# iotester.net
KiCad netlist of a schematic drawn in EAGLE
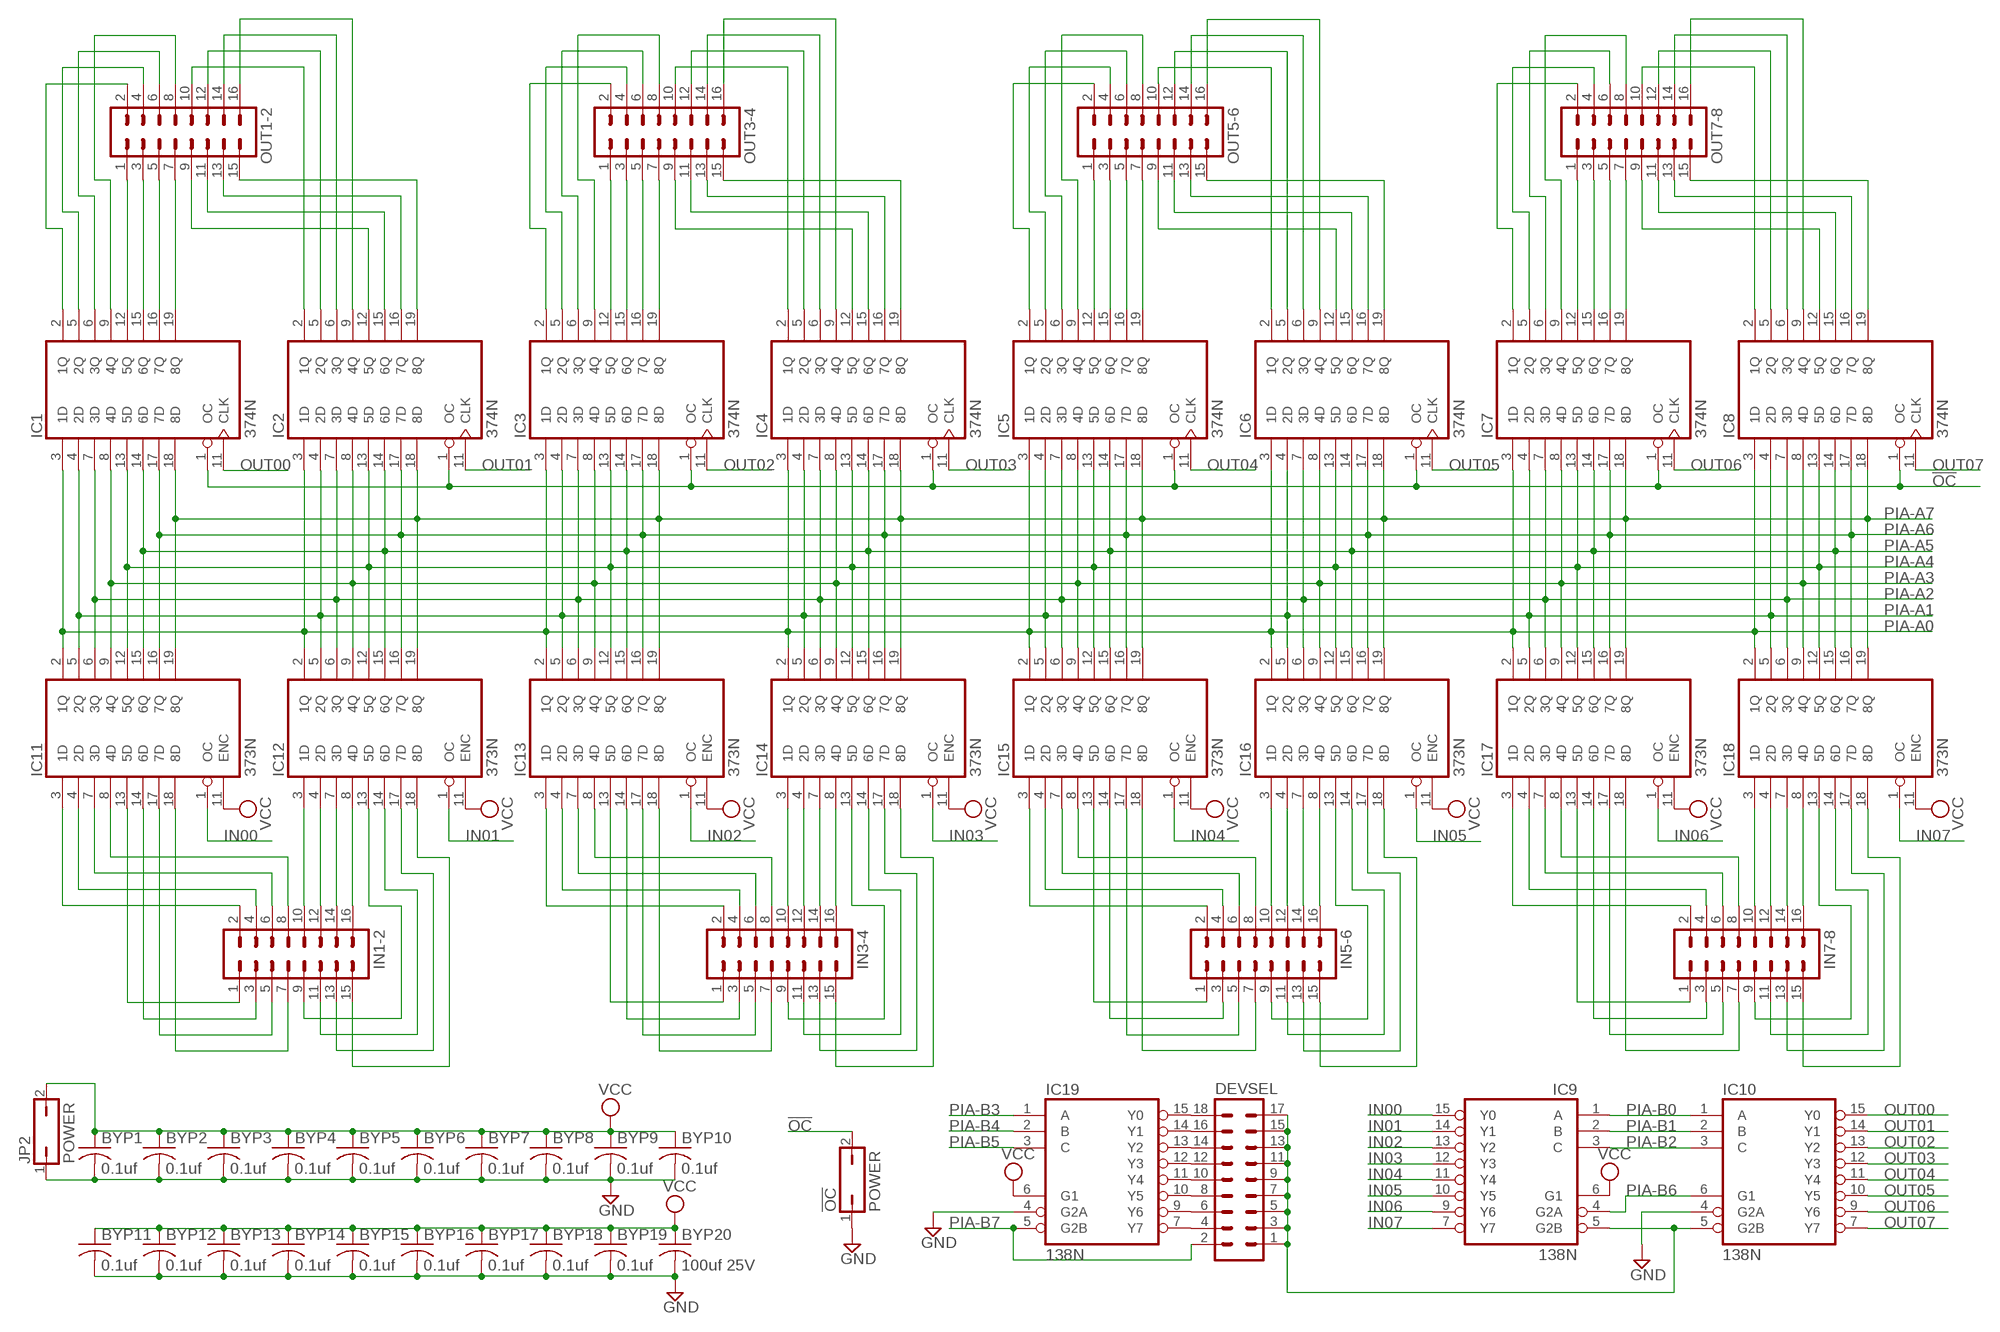
[diagram p0: schematic, sheet 1]
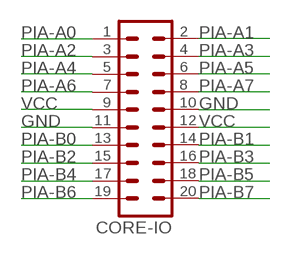
[diagram p1: schematic, sheet 2]

(export (version "E")
  (design (tool "Eeschema 10.0.6"))
  (components
    (comp (ref "!OC")
      (value "POWER")
      (footprint "eagle-import:JP1")
      (libsource (lib "eagle-import") (part "JP1Q"))
    )
    (comp (ref "BYP1")
      (value "0.1uf")
      (footprint "eagle-import:C050-025X075")
      (libsource (lib "eagle-import") (part "C-US050-025X075"))
    )
    (comp (ref "BYP2")
      (value "0.1uf")
      (footprint "eagle-import:C050-025X075")
      (libsource (lib "eagle-import") (part "C-US050-025X075"))
    )
    (comp (ref "BYP3")
      (value "0.1uf")
      (footprint "eagle-import:C050-025X075")
      (libsource (lib "eagle-import") (part "C-US050-025X075"))
    )
    (comp (ref "BYP4")
      (value "0.1uf")
      (footprint "eagle-import:C050-025X075")
      (libsource (lib "eagle-import") (part "C-US050-025X075"))
    )
    (comp (ref "BYP5")
      (value "0.1uf")
      (footprint "eagle-import:C050-025X075")
      (libsource (lib "eagle-import") (part "C-US050-025X075"))
    )
    (comp (ref "BYP6")
      (value "0.1uf")
      (footprint "eagle-import:C050-025X075")
      (libsource (lib "eagle-import") (part "C-US050-025X075"))
    )
    (comp (ref "BYP7")
      (value "0.1uf")
      (footprint "eagle-import:C050-025X075")
      (libsource (lib "eagle-import") (part "C-US050-025X075"))
    )
    (comp (ref "BYP8")
      (value "0.1uf")
      (footprint "eagle-import:C050-025X075")
      (libsource (lib "eagle-import") (part "C-US050-025X075"))
    )
    (comp (ref "BYP9")
      (value "0.1uf")
      (footprint "eagle-import:C050-025X075")
      (libsource (lib "eagle-import") (part "C-US050-025X075"))
    )
    (comp (ref "BYP10")
      (value "0.1uf")
      (footprint "eagle-import:C050-025X075")
      (libsource (lib "eagle-import") (part "C-US050-025X075"))
    )
    (comp (ref "BYP11")
      (value "0.1uf")
      (footprint "eagle-import:C050-025X075")
      (libsource (lib "eagle-import") (part "C-US050-025X075"))
    )
    (comp (ref "BYP12")
      (value "0.1uf")
      (footprint "eagle-import:C050-025X075")
      (libsource (lib "eagle-import") (part "C-US050-025X075"))
    )
    (comp (ref "BYP13")
      (value "0.1uf")
      (footprint "eagle-import:C050-025X075")
      (libsource (lib "eagle-import") (part "C-US050-025X075"))
    )
    (comp (ref "BYP14")
      (value "0.1uf")
      (footprint "eagle-import:C050-025X075")
      (libsource (lib "eagle-import") (part "C-US050-025X075"))
    )
    (comp (ref "BYP15")
      (value "0.1uf")
      (footprint "eagle-import:C050-025X075")
      (libsource (lib "eagle-import") (part "C-US050-025X075"))
    )
    (comp (ref "BYP16")
      (value "0.1uf")
      (footprint "eagle-import:C050-025X075")
      (libsource (lib "eagle-import") (part "C-US050-025X075"))
    )
    (comp (ref "BYP17")
      (value "0.1uf")
      (footprint "eagle-import:C050-025X075")
      (libsource (lib "eagle-import") (part "C-US050-025X075"))
    )
    (comp (ref "BYP18")
      (value "0.1uf")
      (footprint "eagle-import:C050-025X075")
      (libsource (lib "eagle-import") (part "C-US050-025X075"))
    )
    (comp (ref "BYP19")
      (value "0.1uf")
      (footprint "eagle-import:C050-025X075")
      (libsource (lib "eagle-import") (part "C-US050-025X075"))
    )
    (comp (ref "BYP20")
      (value "100uf 25V")
      (footprint "eagle-import:C150-064X183")
      (libsource (lib "eagle-import") (part "C-US150-064X183"))
    )
    (comp (ref "DEVSEL")
      (value "MA09-2")
      (footprint "eagle-import:MA09-2")
      (libsource (lib "eagle-import") (part "MA09-2"))
    )
    (comp (ref "IC1")
      (value "374N")
      (footprint "eagle-import:DIL20")
      (libsource (lib "eagle-import") (part "74374NLS"))
    )
    (comp (ref "IC2")
      (value "374N")
      (footprint "eagle-import:DIL20")
      (libsource (lib "eagle-import") (part "74374NLS"))
    )
    (comp (ref "IC3")
      (value "374N")
      (footprint "eagle-import:DIL20")
      (libsource (lib "eagle-import") (part "74374NLS"))
    )
    (comp (ref "IC4")
      (value "374N")
      (footprint "eagle-import:DIL20")
      (libsource (lib "eagle-import") (part "74374NLS"))
    )
    (comp (ref "IC5")
      (value "374N")
      (footprint "eagle-import:DIL20")
      (libsource (lib "eagle-import") (part "74374NLS"))
    )
    (comp (ref "IC6")
      (value "374N")
      (footprint "eagle-import:DIL20")
      (libsource (lib "eagle-import") (part "74374NLS"))
    )
    (comp (ref "IC7")
      (value "374N")
      (footprint "eagle-import:DIL20")
      (libsource (lib "eagle-import") (part "74374NLS"))
    )
    (comp (ref "IC8")
      (value "374N")
      (footprint "eagle-import:DIL20")
      (libsource (lib "eagle-import") (part "74374NLS"))
    )
    (comp (ref "IC9")
      (value "138N")
      (footprint "eagle-import:DIL16")
      (libsource (lib "eagle-import") (part "74138NLS"))
    )
    (comp (ref "IC10")
      (value "138N")
      (footprint "eagle-import:DIL16")
      (libsource (lib "eagle-import") (part "74138NLS"))
    )
    (comp (ref "IC11")
      (value "373N")
      (footprint "eagle-import:DIL20")
      (libsource (lib "eagle-import") (part "74373NLS"))
    )
    (comp (ref "IC12")
      (value "373N")
      (footprint "eagle-import:DIL20")
      (libsource (lib "eagle-import") (part "74373NLS"))
    )
    (comp (ref "IC13")
      (value "373N")
      (footprint "eagle-import:DIL20")
      (libsource (lib "eagle-import") (part "74373NLS"))
    )
    (comp (ref "IC14")
      (value "373N")
      (footprint "eagle-import:DIL20")
      (libsource (lib "eagle-import") (part "74373NLS"))
    )
    (comp (ref "IC15")
      (value "373N")
      (footprint "eagle-import:DIL20")
      (libsource (lib "eagle-import") (part "74373NLS"))
    )
    (comp (ref "IC16")
      (value "373N")
      (footprint "eagle-import:DIL20")
      (libsource (lib "eagle-import") (part "74373NLS"))
    )
    (comp (ref "IC17")
      (value "373N")
      (footprint "eagle-import:DIL20")
      (libsource (lib "eagle-import") (part "74373NLS"))
    )
    (comp (ref "IC18")
      (value "373N")
      (footprint "eagle-import:DIL20")
      (libsource (lib "eagle-import") (part "74373NLS"))
    )
    (comp (ref "IC19")
      (value "138N")
      (footprint "eagle-import:DIL16")
      (libsource (lib "eagle-import") (part "74138NLS"))
    )
    (comp (ref "IN1-2")
      (value "MA08-2")
      (footprint "eagle-import:MA08-2")
      (libsource (lib "eagle-import") (part "MA08-2"))
    )
    (comp (ref "IN3-4")
      (value "MA08-2")
      (footprint "eagle-import:MA08-2")
      (libsource (lib "eagle-import") (part "MA08-2"))
    )
    (comp (ref "IN5-6")
      (value "MA08-2")
      (footprint "eagle-import:MA08-2")
      (libsource (lib "eagle-import") (part "MA08-2"))
    )
    (comp (ref "IN7-8")
      (value "MA08-2")
      (footprint "eagle-import:MA08-2")
      (libsource (lib "eagle-import") (part "MA08-2"))
    )
    (comp (ref "JP2")
      (value "POWER")
      (footprint "eagle-import:JP1")
      (libsource (lib "eagle-import") (part "JP1Q"))
    )
    (comp (ref "OUT1-2")
      (value "MA08-2")
      (footprint "eagle-import:MA08-2")
      (libsource (lib "eagle-import") (part "MA08-2"))
    )
    (comp (ref "OUT3-4")
      (value "MA08-2")
      (footprint "eagle-import:MA08-2")
      (libsource (lib "eagle-import") (part "MA08-2"))
    )
    (comp (ref "OUT5-6")
      (value "MA08-2")
      (footprint "eagle-import:MA08-2")
      (libsource (lib "eagle-import") (part "MA08-2"))
    )
    (comp (ref "OUT7-8")
      (value "MA08-2")
      (footprint "eagle-import:MA08-2")
      (libsource (lib "eagle-import") (part "MA08-2"))
    )
    (comp (ref "CORE-IO")
      (value "MA10-2")
      (footprint "eagle-import:MA10-2")
      (libsource (lib "eagle-import") (part "MA10-2"))
    )
  )
  (nets
    (net (code "1") (name "GND") (class "Default")
      (node (ref "!OC") (pin "1") (pinfunction "1_1") (pintype "passive"))
      (node (ref "BYP1") (pin "2") (pinfunction "2_2") (pintype "passive"))
      (node (ref "BYP10") (pin "2") (pinfunction "2_2") (pintype "passive"))
      (node (ref "BYP11") (pin "2") (pinfunction "2_2") (pintype "passive"))
      (node (ref "BYP12") (pin "2") (pinfunction "2_2") (pintype "passive"))
      (node (ref "BYP13") (pin "2") (pinfunction "2_2") (pintype "passive"))
      (node (ref "BYP14") (pin "2") (pinfunction "2_2") (pintype "passive"))
      (node (ref "BYP15") (pin "2") (pinfunction "2_2") (pintype "passive"))
      (node (ref "BYP16") (pin "2") (pinfunction "2_2") (pintype "passive"))
      (node (ref "BYP17") (pin "2") (pinfunction "2_2") (pintype "passive"))
      (node (ref "BYP18") (pin "2") (pinfunction "2_2") (pintype "passive"))
      (node (ref "BYP19") (pin "2") (pinfunction "2_2") (pintype "passive"))
      (node (ref "BYP2") (pin "2") (pinfunction "2_2") (pintype "passive"))
      (node (ref "BYP20") (pin "2") (pinfunction "2_2") (pintype "passive"))
      (node (ref "BYP3") (pin "2") (pinfunction "2_2") (pintype "passive"))
      (node (ref "BYP4") (pin "2") (pinfunction "2_2") (pintype "passive"))
      (node (ref "BYP5") (pin "2") (pinfunction "2_2") (pintype "passive"))
      (node (ref "BYP6") (pin "2") (pinfunction "2_2") (pintype "passive"))
      (node (ref "BYP7") (pin "2") (pinfunction "2_2") (pintype "passive"))
      (node (ref "BYP8") (pin "2") (pinfunction "2_2") (pintype "passive"))
      (node (ref "BYP9") (pin "2") (pinfunction "2_2") (pintype "passive"))
      (node (ref "CORE-IO") (pin "10") (pinfunction "10_10") (pintype "passive"))
      (node (ref "CORE-IO") (pin "11") (pinfunction "11_11") (pintype "passive"))
      (node (ref "IC10") (pin "4") (pinfunction "G2A_4") (pintype "input"))
      (node (ref "IC19") (pin "4") (pinfunction "G2A_4") (pintype "input"))
      (node (ref "JP2") (pin "1") (pinfunction "1_1") (pintype "passive"))
    )
    (net (code "2") (name "IN00") (class "Default")
      (node (ref "IC11") (pin "1") (pinfunction "OC_1") (pintype "input"))
      (node (ref "IC9") (pin "15") (pinfunction "Y0_15") (pintype "output"))
    )
    (net (code "3") (name "IN01") (class "Default")
      (node (ref "IC12") (pin "1") (pinfunction "OC_1") (pintype "input"))
      (node (ref "IC9") (pin "14") (pinfunction "Y1_14") (pintype "output"))
    )
    (net (code "4") (name "IN02") (class "Default")
      (node (ref "IC13") (pin "1") (pinfunction "OC_1") (pintype "input"))
      (node (ref "IC9") (pin "13") (pinfunction "Y2_13") (pintype "output"))
    )
    (net (code "5") (name "IN03") (class "Default")
      (node (ref "IC14") (pin "1") (pinfunction "OC_1") (pintype "input"))
      (node (ref "IC9") (pin "12") (pinfunction "Y3_12") (pintype "output"))
    )
    (net (code "6") (name "IN04") (class "Default")
      (node (ref "IC15") (pin "1") (pinfunction "OC_1") (pintype "input"))
      (node (ref "IC9") (pin "11") (pinfunction "Y4_11") (pintype "output"))
    )
    (net (code "7") (name "IN05") (class "Default")
      (node (ref "IC16") (pin "1") (pinfunction "OC_1") (pintype "input"))
      (node (ref "IC9") (pin "10") (pinfunction "Y5_10") (pintype "output"))
    )
    (net (code "8") (name "IN06") (class "Default")
      (node (ref "IC17") (pin "1") (pinfunction "OC_1") (pintype "input"))
      (node (ref "IC9") (pin "9") (pinfunction "Y6_9") (pintype "output"))
    )
    (net (code "9") (name "IN07") (class "Default")
      (node (ref "IC18") (pin "1") (pinfunction "OC_1") (pintype "input"))
      (node (ref "IC9") (pin "7") (pinfunction "Y7_7") (pintype "output"))
    )
    (net (code "10") (name "Net-(IC1A-1Q)") (class "Default")
      (node (ref "IC1") (pin "2") (pinfunction "1Q_2") (pintype "tri_state"))
      (node (ref "OUT1-2") (pin "2") (pinfunction "2_2") (pintype "passive"))
    )
    (net (code "11") (name "Net-(IC1A-2Q)") (class "Default")
      (node (ref "IC1") (pin "5") (pinfunction "2Q_5") (pintype "tri_state"))
      (node (ref "OUT1-2") (pin "4") (pinfunction "4_4") (pintype "passive"))
    )
    (net (code "12") (name "Net-(IC1A-3Q)") (class "Default")
      (node (ref "IC1") (pin "6") (pinfunction "3Q_6") (pintype "tri_state"))
      (node (ref "OUT1-2") (pin "6") (pinfunction "6_6") (pintype "passive"))
    )
    (net (code "13") (name "Net-(IC1A-4Q)") (class "Default")
      (node (ref "IC1") (pin "9") (pinfunction "4Q_9") (pintype "tri_state"))
      (node (ref "OUT1-2") (pin "8") (pinfunction "8_8") (pintype "passive"))
    )
    (net (code "14") (name "Net-(IC1A-5Q)") (class "Default")
      (node (ref "IC1") (pin "12") (pinfunction "5Q_12") (pintype "tri_state"))
      (node (ref "OUT1-2") (pin "1") (pinfunction "1_1") (pintype "passive"))
    )
    (net (code "15") (name "Net-(IC1A-6Q)") (class "Default")
      (node (ref "IC1") (pin "15") (pinfunction "6Q_15") (pintype "tri_state"))
      (node (ref "OUT1-2") (pin "3") (pinfunction "3_3") (pintype "passive"))
    )
    (net (code "16") (name "Net-(IC1A-7Q)") (class "Default")
      (node (ref "IC1") (pin "16") (pinfunction "7Q_16") (pintype "tri_state"))
      (node (ref "OUT1-2") (pin "5") (pinfunction "5_5") (pintype "passive"))
    )
    (net (code "17") (name "Net-(IC1A-8Q)") (class "Default")
      (node (ref "IC1") (pin "19") (pinfunction "8Q_19") (pintype "tri_state"))
      (node (ref "OUT1-2") (pin "7") (pinfunction "7_7") (pintype "passive"))
    )
    (net (code "18") (name "Net-(IC2A-1Q)") (class "Default")
      (node (ref "IC2") (pin "2") (pinfunction "1Q_2") (pintype "tri_state"))
      (node (ref "OUT1-2") (pin "10") (pinfunction "10_10") (pintype "passive"))
    )
    (net (code "19") (name "Net-(IC2A-2Q)") (class "Default")
      (node (ref "IC2") (pin "5") (pinfunction "2Q_5") (pintype "tri_state"))
      (node (ref "OUT1-2") (pin "12") (pinfunction "12_12") (pintype "passive"))
    )
    (net (code "20") (name "Net-(IC2A-3Q)") (class "Default")
      (node (ref "IC2") (pin "6") (pinfunction "3Q_6") (pintype "tri_state"))
      (node (ref "OUT1-2") (pin "14") (pinfunction "14_14") (pintype "passive"))
    )
    (net (code "21") (name "Net-(IC2A-4Q)") (class "Default")
      (node (ref "IC2") (pin "9") (pinfunction "4Q_9") (pintype "tri_state"))
      (node (ref "OUT1-2") (pin "16") (pinfunction "16_16") (pintype "passive"))
    )
    (net (code "22") (name "Net-(IC2A-5Q)") (class "Default")
      (node (ref "IC2") (pin "12") (pinfunction "5Q_12") (pintype "tri_state"))
      (node (ref "OUT1-2") (pin "9") (pinfunction "9_9") (pintype "passive"))
    )
    (net (code "23") (name "Net-(IC2A-6Q)") (class "Default")
      (node (ref "IC2") (pin "15") (pinfunction "6Q_15") (pintype "tri_state"))
      (node (ref "OUT1-2") (pin "11") (pinfunction "11_11") (pintype "passive"))
    )
    (net (code "24") (name "Net-(IC2A-7Q)") (class "Default")
      (node (ref "IC2") (pin "16") (pinfunction "7Q_16") (pintype "tri_state"))
      (node (ref "OUT1-2") (pin "13") (pinfunction "13_13") (pintype "passive"))
    )
    (net (code "25") (name "Net-(IC2A-8Q)") (class "Default")
      (node (ref "IC2") (pin "19") (pinfunction "8Q_19") (pintype "tri_state"))
      (node (ref "OUT1-2") (pin "15") (pinfunction "15_15") (pintype "passive"))
    )
    (net (code "26") (name "Net-(IC3A-1Q)") (class "Default")
      (node (ref "IC3") (pin "2") (pinfunction "1Q_2") (pintype "tri_state"))
      (node (ref "OUT3-4") (pin "2") (pinfunction "2_2") (pintype "passive"))
    )
    (net (code "27") (name "Net-(IC3A-2Q)") (class "Default")
      (node (ref "IC3") (pin "5") (pinfunction "2Q_5") (pintype "tri_state"))
      (node (ref "OUT3-4") (pin "4") (pinfunction "4_4") (pintype "passive"))
    )
    (net (code "28") (name "Net-(IC3A-3Q)") (class "Default")
      (node (ref "IC3") (pin "6") (pinfunction "3Q_6") (pintype "tri_state"))
      (node (ref "OUT3-4") (pin "6") (pinfunction "6_6") (pintype "passive"))
    )
    (net (code "29") (name "Net-(IC3A-4Q)") (class "Default")
      (node (ref "IC3") (pin "9") (pinfunction "4Q_9") (pintype "tri_state"))
      (node (ref "OUT3-4") (pin "8") (pinfunction "8_8") (pintype "passive"))
    )
    (net (code "30") (name "Net-(IC3A-5Q)") (class "Default")
      (node (ref "IC3") (pin "12") (pinfunction "5Q_12") (pintype "tri_state"))
      (node (ref "OUT3-4") (pin "1") (pinfunction "1_1") (pintype "passive"))
    )
    (net (code "31") (name "Net-(IC3A-6Q)") (class "Default")
      (node (ref "IC3") (pin "15") (pinfunction "6Q_15") (pintype "tri_state"))
      (node (ref "OUT3-4") (pin "3") (pinfunction "3_3") (pintype "passive"))
    )
    (net (code "32") (name "Net-(IC3A-7Q)") (class "Default")
      (node (ref "IC3") (pin "16") (pinfunction "7Q_16") (pintype "tri_state"))
      (node (ref "OUT3-4") (pin "5") (pinfunction "5_5") (pintype "passive"))
    )
    (net (code "33") (name "Net-(IC3A-8Q)") (class "Default")
      (node (ref "IC3") (pin "19") (pinfunction "8Q_19") (pintype "tri_state"))
      (node (ref "OUT3-4") (pin "7") (pinfunction "7_7") (pintype "passive"))
    )
    (net (code "34") (name "Net-(IC4A-1Q)") (class "Default")
      (node (ref "IC4") (pin "2") (pinfunction "1Q_2") (pintype "tri_state"))
      (node (ref "OUT3-4") (pin "10") (pinfunction "10_10") (pintype "passive"))
    )
    (net (code "35") (name "Net-(IC4A-2Q)") (class "Default")
      (node (ref "IC4") (pin "5") (pinfunction "2Q_5") (pintype "tri_state"))
      (node (ref "OUT3-4") (pin "12") (pinfunction "12_12") (pintype "passive"))
    )
    (net (code "36") (name "Net-(IC4A-3Q)") (class "Default")
      (node (ref "IC4") (pin "6") (pinfunction "3Q_6") (pintype "tri_state"))
      (node (ref "OUT3-4") (pin "14") (pinfunction "14_14") (pintype "passive"))
    )
    (net (code "37") (name "Net-(IC4A-4Q)") (class "Default")
      (node (ref "IC4") (pin "9") (pinfunction "4Q_9") (pintype "tri_state"))
      (node (ref "OUT3-4") (pin "16") (pinfunction "16_16") (pintype "passive"))
    )
    (net (code "38") (name "Net-(IC4A-5Q)") (class "Default")
      (node (ref "IC4") (pin "12") (pinfunction "5Q_12") (pintype "tri_state"))
      (node (ref "OUT3-4") (pin "9") (pinfunction "9_9") (pintype "passive"))
    )
    (net (code "39") (name "Net-(IC4A-6Q)") (class "Default")
      (node (ref "IC4") (pin "15") (pinfunction "6Q_15") (pintype "tri_state"))
      (node (ref "OUT3-4") (pin "11") (pinfunction "11_11") (pintype "passive"))
    )
    (net (code "40") (name "Net-(IC4A-7Q)") (class "Default")
      (node (ref "IC4") (pin "16") (pinfunction "7Q_16") (pintype "tri_state"))
      (node (ref "OUT3-4") (pin "13") (pinfunction "13_13") (pintype "passive"))
    )
    (net (code "41") (name "Net-(IC4A-8Q)") (class "Default")
      (node (ref "IC4") (pin "19") (pinfunction "8Q_19") (pintype "tri_state"))
      (node (ref "OUT3-4") (pin "15") (pinfunction "15_15") (pintype "passive"))
    )
    (net (code "42") (name "Net-(IC5A-1Q)") (class "Default")
      (node (ref "IC5") (pin "2") (pinfunction "1Q_2") (pintype "tri_state"))
      (node (ref "OUT5-6") (pin "2") (pinfunction "2_2") (pintype "passive"))
    )
    (net (code "43") (name "Net-(IC5A-2Q)") (class "Default")
      (node (ref "IC5") (pin "5") (pinfunction "2Q_5") (pintype "tri_state"))
      (node (ref "OUT5-6") (pin "4") (pinfunction "4_4") (pintype "passive"))
    )
    (net (code "44") (name "Net-(IC5A-3Q)") (class "Default")
      (node (ref "IC5") (pin "6") (pinfunction "3Q_6") (pintype "tri_state"))
      (node (ref "OUT5-6") (pin "6") (pinfunction "6_6") (pintype "passive"))
    )
    (net (code "45") (name "Net-(IC5A-4Q)") (class "Default")
      (node (ref "IC5") (pin "9") (pinfunction "4Q_9") (pintype "tri_state"))
      (node (ref "OUT5-6") (pin "8") (pinfunction "8_8") (pintype "passive"))
    )
    (net (code "46") (name "Net-(IC5A-5Q)") (class "Default")
      (node (ref "IC5") (pin "12") (pinfunction "5Q_12") (pintype "tri_state"))
      (node (ref "OUT5-6") (pin "1") (pinfunction "1_1") (pintype "passive"))
    )
    (net (code "47") (name "Net-(IC5A-6Q)") (class "Default")
      (node (ref "IC5") (pin "15") (pinfunction "6Q_15") (pintype "tri_state"))
      (node (ref "OUT5-6") (pin "3") (pinfunction "3_3") (pintype "passive"))
    )
    (net (code "48") (name "Net-(IC5A-7Q)") (class "Default")
      (node (ref "IC5") (pin "16") (pinfunction "7Q_16") (pintype "tri_state"))
      (node (ref "OUT5-6") (pin "5") (pinfunction "5_5") (pintype "passive"))
    )
    (net (code "49") (name "Net-(IC5A-8Q)") (class "Default")
      (node (ref "IC5") (pin "19") (pinfunction "8Q_19") (pintype "tri_state"))
      (node (ref "OUT5-6") (pin "7") (pinfunction "7_7") (pintype "passive"))
    )
    (net (code "50") (name "Net-(IC6A-1Q)") (class "Default")
      (node (ref "IC6") (pin "2") (pinfunction "1Q_2") (pintype "tri_state"))
      (node (ref "OUT5-6") (pin "10") (pinfunction "10_10") (pintype "passive"))
    )
    (net (code "51") (name "Net-(IC6A-2Q)") (class "Default")
      (node (ref "IC6") (pin "5") (pinfunction "2Q_5") (pintype "tri_state"))
      (node (ref "OUT5-6") (pin "12") (pinfunction "12_12") (pintype "passive"))
    )
    (net (code "52") (name "Net-(IC6A-3Q)") (class "Default")
      (node (ref "IC6") (pin "6") (pinfunction "3Q_6") (pintype "tri_state"))
      (node (ref "OUT5-6") (pin "14") (pinfunction "14_14") (pintype "passive"))
    )
    (net (code "53") (name "Net-(IC6A-4Q)") (class "Default")
      (node (ref "IC6") (pin "9") (pinfunction "4Q_9") (pintype "tri_state"))
      (node (ref "OUT5-6") (pin "16") (pinfunction "16_16") (pintype "passive"))
    )
    (net (code "54") (name "Net-(IC6A-5Q)") (class "Default")
      (node (ref "IC6") (pin "12") (pinfunction "5Q_12") (pintype "tri_state"))
      (node (ref "OUT5-6") (pin "9") (pinfunction "9_9") (pintype "passive"))
    )
    (net (code "55") (name "Net-(IC6A-6Q)") (class "Default")
      (node (ref "IC6") (pin "15") (pinfunction "6Q_15") (pintype "tri_state"))
      (node (ref "OUT5-6") (pin "11") (pinfunction "11_11") (pintype "passive"))
    )
    (net (code "56") (name "Net-(IC6A-7Q)") (class "Default")
      (node (ref "IC6") (pin "16") (pinfunction "7Q_16") (pintype "tri_state"))
      (node (ref "OUT5-6") (pin "13") (pinfunction "13_13") (pintype "passive"))
    )
    (net (code "57") (name "Net-(IC6A-8Q)") (class "Default")
      (node (ref "IC6") (pin "19") (pinfunction "8Q_19") (pintype "tri_state"))
      (node (ref "OUT5-6") (pin "15") (pinfunction "15_15") (pintype "passive"))
    )
    (net (code "58") (name "Net-(IC7A-1Q)") (class "Default")
      (node (ref "IC7") (pin "2") (pinfunction "1Q_2") (pintype "tri_state"))
      (node (ref "OUT7-8") (pin "2") (pinfunction "2_2") (pintype "passive"))
    )
    (net (code "59") (name "Net-(IC7A-2Q)") (class "Default")
      (node (ref "IC7") (pin "5") (pinfunction "2Q_5") (pintype "tri_state"))
      (node (ref "OUT7-8") (pin "4") (pinfunction "4_4") (pintype "passive"))
    )
    (net (code "60") (name "Net-(IC7A-3Q)") (class "Default")
      (node (ref "IC7") (pin "6") (pinfunction "3Q_6") (pintype "tri_state"))
      (node (ref "OUT7-8") (pin "6") (pinfunction "6_6") (pintype "passive"))
    )
    (net (code "61") (name "Net-(IC7A-4Q)") (class "Default")
      (node (ref "IC7") (pin "9") (pinfunction "4Q_9") (pintype "tri_state"))
      (node (ref "OUT7-8") (pin "8") (pinfunction "8_8") (pintype "passive"))
    )
    (net (code "62") (name "Net-(IC7A-5Q)") (class "Default")
      (node (ref "IC7") (pin "12") (pinfunction "5Q_12") (pintype "tri_state"))
      (node (ref "OUT7-8") (pin "1") (pinfunction "1_1") (pintype "passive"))
    )
    (net (code "63") (name "Net-(IC7A-6Q)") (class "Default")
      (node (ref "IC7") (pin "15") (pinfunction "6Q_15") (pintype "tri_state"))
      (node (ref "OUT7-8") (pin "3") (pinfunction "3_3") (pintype "passive"))
    )
    (net (code "64") (name "Net-(IC7A-7Q)") (class "Default")
      (node (ref "IC7") (pin "16") (pinfunction "7Q_16") (pintype "tri_state"))
      (node (ref "OUT7-8") (pin "5") (pinfunction "5_5") (pintype "passive"))
    )
    (net (code "65") (name "Net-(IC7A-8Q)") (class "Default")
      (node (ref "IC7") (pin "19") (pinfunction "8Q_19") (pintype "tri_state"))
      (node (ref "OUT7-8") (pin "7") (pinfunction "7_7") (pintype "passive"))
    )
    (net (code "66") (name "Net-(IC8A-1Q)") (class "Default")
      (node (ref "IC8") (pin "2") (pinfunction "1Q_2") (pintype "tri_state"))
      (node (ref "OUT7-8") (pin "10") (pinfunction "10_10") (pintype "passive"))
    )
    (net (code "67") (name "Net-(IC8A-2Q)") (class "Default")
      (node (ref "IC8") (pin "5") (pinfunction "2Q_5") (pintype "tri_state"))
      (node (ref "OUT7-8") (pin "12") (pinfunction "12_12") (pintype "passive"))
    )
    (net (code "68") (name "Net-(IC8A-3Q)") (class "Default")
      (node (ref "IC8") (pin "6") (pinfunction "3Q_6") (pintype "tri_state"))
      (node (ref "OUT7-8") (pin "14") (pinfunction "14_14") (pintype "passive"))
    )
    (net (code "69") (name "Net-(IC8A-4Q)") (class "Default")
      (node (ref "IC8") (pin "9") (pinfunction "4Q_9") (pintype "tri_state"))
      (node (ref "OUT7-8") (pin "16") (pinfunction "16_16") (pintype "passive"))
    )
    (net (code "70") (name "Net-(IC8A-5Q)") (class "Default")
      (node (ref "IC8") (pin "12") (pinfunction "5Q_12") (pintype "tri_state"))
      (node (ref "OUT7-8") (pin "9") (pinfunction "9_9") (pintype "passive"))
    )
    (net (code "71") (name "Net-(IC8A-6Q)") (class "Default")
      (node (ref "IC8") (pin "15") (pinfunction "6Q_15") (pintype "tri_state"))
      (node (ref "OUT7-8") (pin "11") (pinfunction "11_11") (pintype "passive"))
    )
    (net (code "72") (name "Net-(IC8A-7Q)") (class "Default")
      (node (ref "IC8") (pin "16") (pinfunction "7Q_16") (pintype "tri_state"))
      (node (ref "OUT7-8") (pin "13") (pinfunction "13_13") (pintype "passive"))
    )
    (net (code "73") (name "Net-(IC8A-8Q)") (class "Default")
      (node (ref "IC8") (pin "19") (pinfunction "8Q_19") (pintype "tri_state"))
      (node (ref "OUT7-8") (pin "15") (pinfunction "15_15") (pintype "passive"))
    )
    (net (code "74") (name "Net-(IC10A-G2B)") (class "Default")
      (node (ref "DEVSEL") (pin "1") (pinfunction "1_1") (pintype "passive"))
      (node (ref "DEVSEL") (pin "11") (pinfunction "11_11") (pintype "passive"))
      (node (ref "DEVSEL") (pin "13") (pinfunction "13_13") (pintype "passive"))
      (node (ref "DEVSEL") (pin "15") (pinfunction "15_15") (pintype "passive"))
      (node (ref "DEVSEL") (pin "17") (pinfunction "17_17") (pintype "passive"))
      (node (ref "DEVSEL") (pin "3") (pinfunction "3_3") (pintype "passive"))
      (node (ref "DEVSEL") (pin "5") (pinfunction "5_5") (pintype "passive"))
      (node (ref "DEVSEL") (pin "7") (pinfunction "7_7") (pintype "passive"))
      (node (ref "DEVSEL") (pin "9") (pinfunction "9_9") (pintype "passive"))
      (node (ref "IC10") (pin "5") (pinfunction "G2B_5") (pintype "input"))
      (node (ref "IC9") (pin "5") (pinfunction "G2B_5") (pintype "input"))
    )
    (net (code "75") (name "Net-(IC11A-1D)") (class "Default")
      (node (ref "IC11") (pin "3") (pinfunction "1D_3") (pintype "input"))
      (node (ref "IN1-2") (pin "2") (pinfunction "2_2") (pintype "passive"))
    )
    (net (code "76") (name "Net-(IC11A-2D)") (class "Default")
      (node (ref "IC11") (pin "4") (pinfunction "2D_4") (pintype "input"))
      (node (ref "IN1-2") (pin "4") (pinfunction "4_4") (pintype "passive"))
    )
    (net (code "77") (name "Net-(IC11A-3D)") (class "Default")
      (node (ref "IC11") (pin "7") (pinfunction "3D_7") (pintype "input"))
      (node (ref "IN1-2") (pin "6") (pinfunction "6_6") (pintype "passive"))
    )
    (net (code "78") (name "Net-(IC11A-4D)") (class "Default")
      (node (ref "IC11") (pin "8") (pinfunction "4D_8") (pintype "input"))
      (node (ref "IN1-2") (pin "8") (pinfunction "8_8") (pintype "passive"))
    )
    (net (code "79") (name "Net-(IC11A-5D)") (class "Default")
      (node (ref "IC11") (pin "13") (pinfunction "5D_13") (pintype "input"))
      (node (ref "IN1-2") (pin "1") (pinfunction "1_1") (pintype "passive"))
    )
    (net (code "80") (name "Net-(IC11A-6D)") (class "Default")
      (node (ref "IC11") (pin "14") (pinfunction "6D_14") (pintype "input"))
      (node (ref "IN1-2") (pin "3") (pinfunction "3_3") (pintype "passive"))
    )
    (net (code "81") (name "Net-(IC11A-7D)") (class "Default")
      (node (ref "IC11") (pin "17") (pinfunction "7D_17") (pintype "input"))
      (node (ref "IN1-2") (pin "5") (pinfunction "5_5") (pintype "passive"))
    )
    (net (code "82") (name "Net-(IC11A-8D)") (class "Default")
      (node (ref "IC11") (pin "18") (pinfunction "8D_18") (pintype "input"))
      (node (ref "IN1-2") (pin "7") (pinfunction "7_7") (pintype "passive"))
    )
    (net (code "83") (name "Net-(IC12A-1D)") (class "Default")
      (node (ref "IC12") (pin "3") (pinfunction "1D_3") (pintype "input"))
      (node (ref "IN1-2") (pin "10") (pinfunction "10_10") (pintype "passive"))
    )
    (net (code "84") (name "Net-(IC12A-2D)") (class "Default")
      (node (ref "IC12") (pin "4") (pinfunction "2D_4") (pintype "input"))
      (node (ref "IN1-2") (pin "12") (pinfunction "12_12") (pintype "passive"))
    )
    (net (code "85") (name "Net-(IC12A-3D)") (class "Default")
      (node (ref "IC12") (pin "7") (pinfunction "3D_7") (pintype "input"))
      (node (ref "IN1-2") (pin "14") (pinfunction "14_14") (pintype "passive"))
    )
    (net (code "86") (name "Net-(IC12A-4D)") (class "Default")
      (node (ref "IC12") (pin "8") (pinfunction "4D_8") (pintype "input"))
      (node (ref "IN1-2") (pin "16") (pinfunction "16_16") (pintype "passive"))
    )
    (net (code "87") (name "Net-(IC12A-5D)") (class "Default")
      (node (ref "IC12") (pin "13") (pinfunction "5D_13") (pintype "input"))
      (node (ref "IN1-2") (pin "9") (pinfunction "9_9") (pintype "passive"))
    )
    (net (code "88") (name "Net-(IC12A-6D)") (class "Default")
      (node (ref "IC12") (pin "14") (pinfunction "6D_14") (pintype "input"))
      (node (ref "IN1-2") (pin "11") (pinfunction "11_11") (pintype "passive"))
    )
    (net (code "89") (name "Net-(IC12A-7D)") (class "Default")
      (node (ref "IC12") (pin "17") (pinfunction "7D_17") (pintype "input"))
      (node (ref "IN1-2") (pin "13") (pinfunction "13_13") (pintype "passive"))
    )
    (net (code "90") (name "Net-(IC12A-8D)") (class "Default")
      (node (ref "IC12") (pin "18") (pinfunction "8D_18") (pintype "input"))
      (node (ref "IN1-2") (pin "15") (pinfunction "15_15") (pintype "passive"))
    )
    (net (code "91") (name "Net-(IC13A-1D)") (class "Default")
      (node (ref "IC13") (pin "3") (pinfunction "1D_3") (pintype "input"))
      (node (ref "IN3-4") (pin "2") (pinfunction "2_2") (pintype "passive"))
    )
    (net (code "92") (name "Net-(IC13A-2D)") (class "Default")
      (node (ref "IC13") (pin "4") (pinfunction "2D_4") (pintype "input"))
      (node (ref "IN3-4") (pin "4") (pinfunction "4_4") (pintype "passive"))
    )
    (net (code "93") (name "Net-(IC13A-3D)") (class "Default")
      (node (ref "IC13") (pin "7") (pinfunction "3D_7") (pintype "input"))
      (node (ref "IN3-4") (pin "6") (pinfunction "6_6") (pintype "passive"))
    )
    (net (code "94") (name "Net-(IC13A-4D)") (class "Default")
      (node (ref "IC13") (pin "8") (pinfunction "4D_8") (pintype "input"))
      (node (ref "IN3-4") (pin "8") (pinfunction "8_8") (pintype "passive"))
    )
    (net (code "95") (name "Net-(IC13A-5D)") (class "Default")
      (node (ref "IC13") (pin "13") (pinfunction "5D_13") (pintype "input"))
      (node (ref "IN3-4") (pin "1") (pinfunction "1_1") (pintype "passive"))
    )
    (net (code "96") (name "Net-(IC13A-6D)") (class "Default")
      (node (ref "IC13") (pin "14") (pinfunction "6D_14") (pintype "input"))
      (node (ref "IN3-4") (pin "3") (pinfunction "3_3") (pintype "passive"))
    )
    (net (code "97") (name "Net-(IC13A-7D)") (class "Default")
      (node (ref "IC13") (pin "17") (pinfunction "7D_17") (pintype "input"))
      (node (ref "IN3-4") (pin "5") (pinfunction "5_5") (pintype "passive"))
    )
    (net (code "98") (name "Net-(IC13A-8D)") (class "Default")
      (node (ref "IC13") (pin "18") (pinfunction "8D_18") (pintype "input"))
      (node (ref "IN3-4") (pin "7") (pinfunction "7_7") (pintype "passive"))
    )
    (net (code "99") (name "Net-(IC14A-1D)") (class "Default")
      (node (ref "IC14") (pin "3") (pinfunction "1D_3") (pintype "input"))
      (node (ref "IN3-4") (pin "10") (pinfunction "10_10") (pintype "passive"))
    )
    (net (code "100") (name "Net-(IC14A-2D)") (class "Default")
      (node (ref "IC14") (pin "4") (pinfunction "2D_4") (pintype "input"))
      (node (ref "IN3-4") (pin "12") (pinfunction "12_12") (pintype "passive"))
    )
    (net (code "101") (name "Net-(IC14A-3D)") (class "Default")
      (node (ref "IC14") (pin "7") (pinfunction "3D_7") (pintype "input"))
      (node (ref "IN3-4") (pin "14") (pinfunction "14_14") (pintype "passive"))
    )
    (net (code "102") (name "Net-(IC14A-4D)") (class "Default")
      (node (ref "IC14") (pin "8") (pinfunction "4D_8") (pintype "input"))
      (node (ref "IN3-4") (pin "16") (pinfunction "16_16") (pintype "passive"))
    )
    (net (code "103") (name "Net-(IC14A-5D)") (class "Default")
      (node (ref "IC14") (pin "13") (pinfunction "5D_13") (pintype "input"))
      (node (ref "IN3-4") (pin "9") (pinfunction "9_9") (pintype "passive"))
    )
    (net (code "104") (name "Net-(IC14A-6D)") (class "Default")
      (node (ref "IC14") (pin "14") (pinfunction "6D_14") (pintype "input"))
      (node (ref "IN3-4") (pin "11") (pinfunction "11_11") (pintype "passive"))
    )
    (net (code "105") (name "Net-(IC14A-7D)") (class "Default")
      (node (ref "IC14") (pin "17") (pinfunction "7D_17") (pintype "input"))
      (node (ref "IN3-4") (pin "13") (pinfunction "13_13") (pintype "passive"))
    )
    (net (code "106") (name "Net-(IC14A-8D)") (class "Default")
      (node (ref "IC14") (pin "18") (pinfunction "8D_18") (pintype "input"))
      (node (ref "IN3-4") (pin "15") (pinfunction "15_15") (pintype "passive"))
    )
    (net (code "107") (name "Net-(IC15A-1D)") (class "Default")
      (node (ref "IC15") (pin "3") (pinfunction "1D_3") (pintype "input"))
      (node (ref "IN5-6") (pin "2") (pinfunction "2_2") (pintype "passive"))
    )
    (net (code "108") (name "Net-(IC15A-2D)") (class "Default")
      (node (ref "IC15") (pin "4") (pinfunction "2D_4") (pintype "input"))
      (node (ref "IN5-6") (pin "4") (pinfunction "4_4") (pintype "passive"))
    )
    (net (code "109") (name "Net-(IC15A-3D)") (class "Default")
      (node (ref "IC15") (pin "7") (pinfunction "3D_7") (pintype "input"))
      (node (ref "IN5-6") (pin "6") (pinfunction "6_6") (pintype "passive"))
    )
    (net (code "110") (name "Net-(IC15A-4D)") (class "Default")
      (node (ref "IC15") (pin "8") (pinfunction "4D_8") (pintype "input"))
      (node (ref "IN5-6") (pin "8") (pinfunction "8_8") (pintype "passive"))
    )
    (net (code "111") (name "Net-(IC15A-5D)") (class "Default")
      (node (ref "IC15") (pin "13") (pinfunction "5D_13") (pintype "input"))
      (node (ref "IN5-6") (pin "1") (pinfunction "1_1") (pintype "passive"))
    )
    (net (code "112") (name "Net-(IC15A-6D)") (class "Default")
      (node (ref "IC15") (pin "14") (pinfunction "6D_14") (pintype "input"))
      (node (ref "IN5-6") (pin "3") (pinfunction "3_3") (pintype "passive"))
    )
    (net (code "113") (name "Net-(IC15A-7D)") (class "Default")
      (node (ref "IC15") (pin "17") (pinfunction "7D_17") (pintype "input"))
      (node (ref "IN5-6") (pin "5") (pinfunction "5_5") (pintype "passive"))
    )
    (net (code "114") (name "Net-(IC15A-8D)") (class "Default")
      (node (ref "IC15") (pin "18") (pinfunction "8D_18") (pintype "input"))
      (node (ref "IN5-6") (pin "7") (pinfunction "7_7") (pintype "passive"))
    )
    (net (code "115") (name "Net-(IC16A-1D)") (class "Default")
      (node (ref "IC16") (pin "3") (pinfunction "1D_3") (pintype "input"))
      (node (ref "IN5-6") (pin "10") (pinfunction "10_10") (pintype "passive"))
    )
    (net (code "116") (name "Net-(IC16A-2D)") (class "Default")
      (node (ref "IC16") (pin "4") (pinfunction "2D_4") (pintype "input"))
      (node (ref "IN5-6") (pin "12") (pinfunction "12_12") (pintype "passive"))
    )
    (net (code "117") (name "Net-(IC16A-3D)") (class "Default")
      (node (ref "IC16") (pin "7") (pinfunction "3D_7") (pintype "input"))
      (node (ref "IN5-6") (pin "14") (pinfunction "14_14") (pintype "passive"))
    )
    (net (code "118") (name "Net-(IC16A-4D)") (class "Default")
      (node (ref "IC16") (pin "8") (pinfunction "4D_8") (pintype "input"))
      (node (ref "IN5-6") (pin "16") (pinfunction "16_16") (pintype "passive"))
    )
    (net (code "119") (name "Net-(IC16A-5D)") (class "Default")
      (node (ref "IC16") (pin "13") (pinfunction "5D_13") (pintype "input"))
      (node (ref "IN5-6") (pin "9") (pinfunction "9_9") (pintype "passive"))
    )
    (net (code "120") (name "Net-(IC16A-6D)") (class "Default")
      (node (ref "IC16") (pin "14") (pinfunction "6D_14") (pintype "input"))
      (node (ref "IN5-6") (pin "11") (pinfunction "11_11") (pintype "passive"))
    )
    (net (code "121") (name "Net-(IC16A-7D)") (class "Default")
      (node (ref "IC16") (pin "17") (pinfunction "7D_17") (pintype "input"))
      (node (ref "IN5-6") (pin "13") (pinfunction "13_13") (pintype "passive"))
    )
    (net (code "122") (name "Net-(IC16A-8D)") (class "Default")
      (node (ref "IC16") (pin "18") (pinfunction "8D_18") (pintype "input"))
      (node (ref "IN5-6") (pin "15") (pinfunction "15_15") (pintype "passive"))
    )
    (net (code "123") (name "Net-(IC17A-1D)") (class "Default")
      (node (ref "IC17") (pin "3") (pinfunction "1D_3") (pintype "input"))
      (node (ref "IN7-8") (pin "2") (pinfunction "2_2") (pintype "passive"))
    )
    (net (code "124") (name "Net-(IC17A-2D)") (class "Default")
      (node (ref "IC17") (pin "4") (pinfunction "2D_4") (pintype "input"))
      (node (ref "IN7-8") (pin "4") (pinfunction "4_4") (pintype "passive"))
    )
    (net (code "125") (name "Net-(IC17A-3D)") (class "Default")
      (node (ref "IC17") (pin "7") (pinfunction "3D_7") (pintype "input"))
      (node (ref "IN7-8") (pin "6") (pinfunction "6_6") (pintype "passive"))
    )
    (net (code "126") (name "Net-(IC17A-4D)") (class "Default")
      (node (ref "IC17") (pin "8") (pinfunction "4D_8") (pintype "input"))
      (node (ref "IN7-8") (pin "8") (pinfunction "8_8") (pintype "passive"))
    )
    (net (code "127") (name "Net-(IC17A-5D)") (class "Default")
      (node (ref "IC17") (pin "13") (pinfunction "5D_13") (pintype "input"))
      (node (ref "IN7-8") (pin "1") (pinfunction "1_1") (pintype "passive"))
    )
    (net (code "128") (name "Net-(IC17A-6D)") (class "Default")
      (node (ref "IC17") (pin "14") (pinfunction "6D_14") (pintype "input"))
      (node (ref "IN7-8") (pin "3") (pinfunction "3_3") (pintype "passive"))
    )
    (net (code "129") (name "Net-(IC17A-7D)") (class "Default")
      (node (ref "IC17") (pin "17") (pinfunction "7D_17") (pintype "input"))
      (node (ref "IN7-8") (pin "5") (pinfunction "5_5") (pintype "passive"))
    )
    (net (code "130") (name "Net-(IC17A-8D)") (class "Default")
      (node (ref "IC17") (pin "18") (pinfunction "8D_18") (pintype "input"))
      (node (ref "IN7-8") (pin "7") (pinfunction "7_7") (pintype "passive"))
    )
    (net (code "131") (name "Net-(IC18A-1D)") (class "Default")
      (node (ref "IC18") (pin "3") (pinfunction "1D_3") (pintype "input"))
      (node (ref "IN7-8") (pin "10") (pinfunction "10_10") (pintype "passive"))
    )
    (net (code "132") (name "Net-(IC18A-2D)") (class "Default")
      (node (ref "IC18") (pin "4") (pinfunction "2D_4") (pintype "input"))
      (node (ref "IN7-8") (pin "12") (pinfunction "12_12") (pintype "passive"))
    )
    (net (code "133") (name "Net-(IC18A-3D)") (class "Default")
      (node (ref "IC18") (pin "7") (pinfunction "3D_7") (pintype "input"))
      (node (ref "IN7-8") (pin "14") (pinfunction "14_14") (pintype "passive"))
    )
    (net (code "134") (name "Net-(IC18A-4D)") (class "Default")
      (node (ref "IC18") (pin "8") (pinfunction "4D_8") (pintype "input"))
      (node (ref "IN7-8") (pin "16") (pinfunction "16_16") (pintype "passive"))
    )
    (net (code "135") (name "Net-(IC18A-5D)") (class "Default")
      (node (ref "IC18") (pin "13") (pinfunction "5D_13") (pintype "input"))
      (node (ref "IN7-8") (pin "9") (pinfunction "9_9") (pintype "passive"))
    )
    (net (code "136") (name "Net-(IC18A-6D)") (class "Default")
      (node (ref "IC18") (pin "14") (pinfunction "6D_14") (pintype "input"))
      (node (ref "IN7-8") (pin "11") (pinfunction "11_11") (pintype "passive"))
    )
    (net (code "137") (name "Net-(IC18A-7D)") (class "Default")
      (node (ref "IC18") (pin "17") (pinfunction "7D_17") (pintype "input"))
      (node (ref "IN7-8") (pin "13") (pinfunction "13_13") (pintype "passive"))
    )
    (net (code "138") (name "Net-(IC18A-8D)") (class "Default")
      (node (ref "IC18") (pin "18") (pinfunction "8D_18") (pintype "input"))
      (node (ref "IN7-8") (pin "15") (pinfunction "15_15") (pintype "passive"))
    )
    (net (code "139") (name "Net-(IC19A-Y0)") (class "Default")
      (node (ref "DEVSEL") (pin "18") (pinfunction "18_18") (pintype "passive"))
      (node (ref "IC19") (pin "15") (pinfunction "Y0_15") (pintype "output"))
    )
    (net (code "140") (name "Net-(IC19A-Y1)") (class "Default")
      (node (ref "DEVSEL") (pin "16") (pinfunction "16_16") (pintype "passive"))
      (node (ref "IC19") (pin "14") (pinfunction "Y1_14") (pintype "output"))
    )
    (net (code "141") (name "Net-(IC19A-Y2)") (class "Default")
      (node (ref "DEVSEL") (pin "14") (pinfunction "14_14") (pintype "passive"))
      (node (ref "IC19") (pin "13") (pinfunction "Y2_13") (pintype "output"))
    )
    (net (code "142") (name "Net-(IC19A-Y3)") (class "Default")
      (node (ref "DEVSEL") (pin "12") (pinfunction "12_12") (pintype "passive"))
      (node (ref "IC19") (pin "12") (pinfunction "Y3_12") (pintype "output"))
    )
    (net (code "143") (name "Net-(IC19A-Y4)") (class "Default")
      (node (ref "DEVSEL") (pin "10") (pinfunction "10_10") (pintype "passive"))
      (node (ref "IC19") (pin "11") (pinfunction "Y4_11") (pintype "output"))
    )
    (net (code "144") (name "Net-(IC19A-Y5)") (class "Default")
      (node (ref "DEVSEL") (pin "8") (pinfunction "8_8") (pintype "passive"))
      (node (ref "IC19") (pin "10") (pinfunction "Y5_10") (pintype "output"))
    )
    (net (code "145") (name "Net-(IC19A-Y6)") (class "Default")
      (node (ref "DEVSEL") (pin "6") (pinfunction "6_6") (pintype "passive"))
      (node (ref "IC19") (pin "9") (pinfunction "Y6_9") (pintype "output"))
    )
    (net (code "146") (name "Net-(IC19A-Y7)") (class "Default")
      (node (ref "DEVSEL") (pin "4") (pinfunction "4_4") (pintype "passive"))
      (node (ref "IC19") (pin "7") (pinfunction "Y7_7") (pintype "output"))
    )
    (net (code "147") (name "OUT00") (class "Default")
      (node (ref "IC1") (pin "11") (pinfunction "CLK_11") (pintype "input"))
      (node (ref "IC10") (pin "15") (pinfunction "Y0_15") (pintype "output"))
    )
    (net (code "148") (name "OUT01") (class "Default")
      (node (ref "IC10") (pin "14") (pinfunction "Y1_14") (pintype "output"))
      (node (ref "IC2") (pin "11") (pinfunction "CLK_11") (pintype "input"))
    )
    (net (code "149") (name "OUT02") (class "Default")
      (node (ref "IC10") (pin "13") (pinfunction "Y2_13") (pintype "output"))
      (node (ref "IC3") (pin "11") (pinfunction "CLK_11") (pintype "input"))
    )
    (net (code "150") (name "OUT03") (class "Default")
      (node (ref "IC10") (pin "12") (pinfunction "Y3_12") (pintype "output"))
      (node (ref "IC4") (pin "11") (pinfunction "CLK_11") (pintype "input"))
    )
    (net (code "151") (name "OUT04") (class "Default")
      (node (ref "IC10") (pin "11") (pinfunction "Y4_11") (pintype "output"))
      (node (ref "IC5") (pin "11") (pinfunction "CLK_11") (pintype "input"))
    )
    (net (code "152") (name "OUT05") (class "Default")
      (node (ref "IC10") (pin "10") (pinfunction "Y5_10") (pintype "output"))
      (node (ref "IC6") (pin "11") (pinfunction "CLK_11") (pintype "input"))
    )
    (net (code "153") (name "OUT06") (class "Default")
      (node (ref "IC10") (pin "9") (pinfunction "Y6_9") (pintype "output"))
      (node (ref "IC7") (pin "11") (pinfunction "CLK_11") (pintype "input"))
    )
    (net (code "154") (name "OUT07") (class "Default")
      (node (ref "IC10") (pin "7") (pinfunction "Y7_7") (pintype "output"))
      (node (ref "IC8") (pin "11") (pinfunction "CLK_11") (pintype "input"))
    )
    (net (code "155") (name "PIA-A0") (class "Default")
      (node (ref "CORE-IO") (pin "1") (pinfunction "1_1") (pintype "passive"))
      (node (ref "IC1") (pin "3") (pinfunction "1D_3") (pintype "input"))
      (node (ref "IC11") (pin "2") (pinfunction "1Q_2") (pintype "tri_state"))
      (node (ref "IC12") (pin "2") (pinfunction "1Q_2") (pintype "tri_state"))
      (node (ref "IC13") (pin "2") (pinfunction "1Q_2") (pintype "tri_state"))
      (node (ref "IC14") (pin "2") (pinfunction "1Q_2") (pintype "tri_state"))
      (node (ref "IC15") (pin "2") (pinfunction "1Q_2") (pintype "tri_state"))
      (node (ref "IC16") (pin "2") (pinfunction "1Q_2") (pintype "tri_state"))
      (node (ref "IC17") (pin "2") (pinfunction "1Q_2") (pintype "tri_state"))
      (node (ref "IC18") (pin "2") (pinfunction "1Q_2") (pintype "tri_state"))
      (node (ref "IC2") (pin "3") (pinfunction "1D_3") (pintype "input"))
      (node (ref "IC3") (pin "3") (pinfunction "1D_3") (pintype "input"))
      (node (ref "IC4") (pin "3") (pinfunction "1D_3") (pintype "input"))
      (node (ref "IC5") (pin "3") (pinfunction "1D_3") (pintype "input"))
      (node (ref "IC6") (pin "3") (pinfunction "1D_3") (pintype "input"))
      (node (ref "IC7") (pin "3") (pinfunction "1D_3") (pintype "input"))
      (node (ref "IC8") (pin "3") (pinfunction "1D_3") (pintype "input"))
    )
    (net (code "156") (name "PIA-A1") (class "Default")
      (node (ref "CORE-IO") (pin "2") (pinfunction "2_2") (pintype "passive"))
      (node (ref "IC1") (pin "4") (pinfunction "2D_4") (pintype "input"))
      (node (ref "IC11") (pin "5") (pinfunction "2Q_5") (pintype "tri_state"))
      (node (ref "IC12") (pin "5") (pinfunction "2Q_5") (pintype "tri_state"))
      (node (ref "IC13") (pin "5") (pinfunction "2Q_5") (pintype "tri_state"))
      (node (ref "IC14") (pin "5") (pinfunction "2Q_5") (pintype "tri_state"))
      (node (ref "IC15") (pin "5") (pinfunction "2Q_5") (pintype "tri_state"))
      (node (ref "IC16") (pin "5") (pinfunction "2Q_5") (pintype "tri_state"))
      (node (ref "IC17") (pin "5") (pinfunction "2Q_5") (pintype "tri_state"))
      (node (ref "IC18") (pin "5") (pinfunction "2Q_5") (pintype "tri_state"))
      (node (ref "IC2") (pin "4") (pinfunction "2D_4") (pintype "input"))
      (node (ref "IC3") (pin "4") (pinfunction "2D_4") (pintype "input"))
      (node (ref "IC4") (pin "4") (pinfunction "2D_4") (pintype "input"))
      (node (ref "IC5") (pin "4") (pinfunction "2D_4") (pintype "input"))
      (node (ref "IC6") (pin "4") (pinfunction "2D_4") (pintype "input"))
      (node (ref "IC7") (pin "4") (pinfunction "2D_4") (pintype "input"))
      (node (ref "IC8") (pin "4") (pinfunction "2D_4") (pintype "input"))
    )
    (net (code "157") (name "PIA-A2") (class "Default")
      (node (ref "CORE-IO") (pin "3") (pinfunction "3_3") (pintype "passive"))
      (node (ref "IC1") (pin "7") (pinfunction "3D_7") (pintype "input"))
      (node (ref "IC11") (pin "6") (pinfunction "3Q_6") (pintype "tri_state"))
      (node (ref "IC12") (pin "6") (pinfunction "3Q_6") (pintype "tri_state"))
      (node (ref "IC13") (pin "6") (pinfunction "3Q_6") (pintype "tri_state"))
      (node (ref "IC14") (pin "6") (pinfunction "3Q_6") (pintype "tri_state"))
      (node (ref "IC15") (pin "6") (pinfunction "3Q_6") (pintype "tri_state"))
      (node (ref "IC16") (pin "6") (pinfunction "3Q_6") (pintype "tri_state"))
      (node (ref "IC17") (pin "6") (pinfunction "3Q_6") (pintype "tri_state"))
      (node (ref "IC18") (pin "6") (pinfunction "3Q_6") (pintype "tri_state"))
      (node (ref "IC2") (pin "7") (pinfunction "3D_7") (pintype "input"))
      (node (ref "IC3") (pin "7") (pinfunction "3D_7") (pintype "input"))
      (node (ref "IC4") (pin "7") (pinfunction "3D_7") (pintype "input"))
      (node (ref "IC5") (pin "7") (pinfunction "3D_7") (pintype "input"))
      (node (ref "IC6") (pin "7") (pinfunction "3D_7") (pintype "input"))
      (node (ref "IC7") (pin "7") (pinfunction "3D_7") (pintype "input"))
      (node (ref "IC8") (pin "7") (pinfunction "3D_7") (pintype "input"))
    )
    (net (code "158") (name "PIA-A3") (class "Default")
      (node (ref "CORE-IO") (pin "4") (pinfunction "4_4") (pintype "passive"))
      (node (ref "IC1") (pin "8") (pinfunction "4D_8") (pintype "input"))
      (node (ref "IC11") (pin "9") (pinfunction "4Q_9") (pintype "tri_state"))
      (node (ref "IC12") (pin "9") (pinfunction "4Q_9") (pintype "tri_state"))
      (node (ref "IC13") (pin "9") (pinfunction "4Q_9") (pintype "tri_state"))
      (node (ref "IC14") (pin "9") (pinfunction "4Q_9") (pintype "tri_state"))
      (node (ref "IC15") (pin "9") (pinfunction "4Q_9") (pintype "tri_state"))
      (node (ref "IC16") (pin "9") (pinfunction "4Q_9") (pintype "tri_state"))
      (node (ref "IC17") (pin "9") (pinfunction "4Q_9") (pintype "tri_state"))
      (node (ref "IC18") (pin "9") (pinfunction "4Q_9") (pintype "tri_state"))
      (node (ref "IC2") (pin "8") (pinfunction "4D_8") (pintype "input"))
      (node (ref "IC3") (pin "8") (pinfunction "4D_8") (pintype "input"))
      (node (ref "IC4") (pin "8") (pinfunction "4D_8") (pintype "input"))
      (node (ref "IC5") (pin "8") (pinfunction "4D_8") (pintype "input"))
      (node (ref "IC6") (pin "8") (pinfunction "4D_8") (pintype "input"))
      (node (ref "IC7") (pin "8") (pinfunction "4D_8") (pintype "input"))
      (node (ref "IC8") (pin "8") (pinfunction "4D_8") (pintype "input"))
    )
    (net (code "159") (name "PIA-A4") (class "Default")
      (node (ref "CORE-IO") (pin "5") (pinfunction "5_5") (pintype "passive"))
      (node (ref "IC1") (pin "13") (pinfunction "5D_13") (pintype "input"))
      (node (ref "IC11") (pin "12") (pinfunction "5Q_12") (pintype "tri_state"))
      (node (ref "IC12") (pin "12") (pinfunction "5Q_12") (pintype "tri_state"))
      (node (ref "IC13") (pin "12") (pinfunction "5Q_12") (pintype "tri_state"))
      (node (ref "IC14") (pin "12") (pinfunction "5Q_12") (pintype "tri_state"))
      (node (ref "IC15") (pin "12") (pinfunction "5Q_12") (pintype "tri_state"))
      (node (ref "IC16") (pin "12") (pinfunction "5Q_12") (pintype "tri_state"))
      (node (ref "IC17") (pin "12") (pinfunction "5Q_12") (pintype "tri_state"))
      (node (ref "IC18") (pin "12") (pinfunction "5Q_12") (pintype "tri_state"))
      (node (ref "IC2") (pin "13") (pinfunction "5D_13") (pintype "input"))
      (node (ref "IC3") (pin "13") (pinfunction "5D_13") (pintype "input"))
      (node (ref "IC4") (pin "13") (pinfunction "5D_13") (pintype "input"))
      (node (ref "IC5") (pin "13") (pinfunction "5D_13") (pintype "input"))
      (node (ref "IC6") (pin "13") (pinfunction "5D_13") (pintype "input"))
      (node (ref "IC7") (pin "13") (pinfunction "5D_13") (pintype "input"))
      (node (ref "IC8") (pin "13") (pinfunction "5D_13") (pintype "input"))
    )
    (net (code "160") (name "PIA-A5") (class "Default")
      (node (ref "CORE-IO") (pin "6") (pinfunction "6_6") (pintype "passive"))
      (node (ref "IC1") (pin "14") (pinfunction "6D_14") (pintype "input"))
      (node (ref "IC11") (pin "15") (pinfunction "6Q_15") (pintype "tri_state"))
      (node (ref "IC12") (pin "15") (pinfunction "6Q_15") (pintype "tri_state"))
      (node (ref "IC13") (pin "15") (pinfunction "6Q_15") (pintype "tri_state"))
      (node (ref "IC14") (pin "15") (pinfunction "6Q_15") (pintype "tri_state"))
      (node (ref "IC15") (pin "15") (pinfunction "6Q_15") (pintype "tri_state"))
      (node (ref "IC16") (pin "15") (pinfunction "6Q_15") (pintype "tri_state"))
      (node (ref "IC17") (pin "15") (pinfunction "6Q_15") (pintype "tri_state"))
      (node (ref "IC18") (pin "15") (pinfunction "6Q_15") (pintype "tri_state"))
      (node (ref "IC2") (pin "14") (pinfunction "6D_14") (pintype "input"))
      (node (ref "IC3") (pin "14") (pinfunction "6D_14") (pintype "input"))
      (node (ref "IC4") (pin "14") (pinfunction "6D_14") (pintype "input"))
      (node (ref "IC5") (pin "14") (pinfunction "6D_14") (pintype "input"))
      (node (ref "IC6") (pin "14") (pinfunction "6D_14") (pintype "input"))
      (node (ref "IC7") (pin "14") (pinfunction "6D_14") (pintype "input"))
      (node (ref "IC8") (pin "14") (pinfunction "6D_14") (pintype "input"))
    )
    (net (code "161") (name "PIA-A6") (class "Default")
      (node (ref "CORE-IO") (pin "7") (pinfunction "7_7") (pintype "passive"))
      (node (ref "IC1") (pin "17") (pinfunction "7D_17") (pintype "input"))
      (node (ref "IC11") (pin "16") (pinfunction "7Q_16") (pintype "tri_state"))
      (node (ref "IC12") (pin "16") (pinfunction "7Q_16") (pintype "tri_state"))
      (node (ref "IC13") (pin "16") (pinfunction "7Q_16") (pintype "tri_state"))
      (node (ref "IC14") (pin "16") (pinfunction "7Q_16") (pintype "tri_state"))
      (node (ref "IC15") (pin "16") (pinfunction "7Q_16") (pintype "tri_state"))
      (node (ref "IC16") (pin "16") (pinfunction "7Q_16") (pintype "tri_state"))
      (node (ref "IC17") (pin "16") (pinfunction "7Q_16") (pintype "tri_state"))
      (node (ref "IC18") (pin "16") (pinfunction "7Q_16") (pintype "tri_state"))
      (node (ref "IC2") (pin "17") (pinfunction "7D_17") (pintype "input"))
      (node (ref "IC3") (pin "17") (pinfunction "7D_17") (pintype "input"))
      (node (ref "IC4") (pin "17") (pinfunction "7D_17") (pintype "input"))
      (node (ref "IC5") (pin "17") (pinfunction "7D_17") (pintype "input"))
      (node (ref "IC6") (pin "17") (pinfunction "7D_17") (pintype "input"))
      (node (ref "IC7") (pin "17") (pinfunction "7D_17") (pintype "input"))
      (node (ref "IC8") (pin "17") (pinfunction "7D_17") (pintype "input"))
    )
    (net (code "162") (name "PIA-A7") (class "Default")
      (node (ref "CORE-IO") (pin "8") (pinfunction "8_8") (pintype "passive"))
      (node (ref "IC1") (pin "18") (pinfunction "8D_18") (pintype "input"))
      (node (ref "IC11") (pin "19") (pinfunction "8Q_19") (pintype "tri_state"))
      (node (ref "IC12") (pin "19") (pinfunction "8Q_19") (pintype "tri_state"))
      (node (ref "IC13") (pin "19") (pinfunction "8Q_19") (pintype "tri_state"))
      (node (ref "IC14") (pin "19") (pinfunction "8Q_19") (pintype "tri_state"))
      (node (ref "IC15") (pin "19") (pinfunction "8Q_19") (pintype "tri_state"))
      (node (ref "IC16") (pin "19") (pinfunction "8Q_19") (pintype "tri_state"))
      (node (ref "IC17") (pin "19") (pinfunction "8Q_19") (pintype "tri_state"))
      (node (ref "IC18") (pin "19") (pinfunction "8Q_19") (pintype "tri_state"))
      (node (ref "IC2") (pin "18") (pinfunction "8D_18") (pintype "input"))
      (node (ref "IC3") (pin "18") (pinfunction "8D_18") (pintype "input"))
      (node (ref "IC4") (pin "18") (pinfunction "8D_18") (pintype "input"))
      (node (ref "IC5") (pin "18") (pinfunction "8D_18") (pintype "input"))
      (node (ref "IC6") (pin "18") (pinfunction "8D_18") (pintype "input"))
      (node (ref "IC7") (pin "18") (pinfunction "8D_18") (pintype "input"))
      (node (ref "IC8") (pin "18") (pinfunction "8D_18") (pintype "input"))
    )
    (net (code "163") (name "PIA-B0") (class "Default")
      (node (ref "CORE-IO") (pin "13") (pinfunction "13_13") (pintype "passive"))
      (node (ref "IC10") (pin "1") (pinfunction "A_1") (pintype "input"))
      (node (ref "IC9") (pin "1") (pinfunction "A_1") (pintype "input"))
    )
    (net (code "164") (name "PIA-B1") (class "Default")
      (node (ref "CORE-IO") (pin "14") (pinfunction "14_14") (pintype "passive"))
      (node (ref "IC10") (pin "2") (pinfunction "B_2") (pintype "input"))
      (node (ref "IC9") (pin "2") (pinfunction "B_2") (pintype "input"))
    )
    (net (code "165") (name "PIA-B2") (class "Default")
      (node (ref "CORE-IO") (pin "15") (pinfunction "15_15") (pintype "passive"))
      (node (ref "IC10") (pin "3") (pinfunction "C_3") (pintype "input"))
      (node (ref "IC9") (pin "3") (pinfunction "C_3") (pintype "input"))
    )
    (net (code "166") (name "PIA-B3") (class "Default")
      (node (ref "CORE-IO") (pin "16") (pinfunction "16_16") (pintype "passive"))
      (node (ref "IC19") (pin "1") (pinfunction "A_1") (pintype "input"))
    )
    (net (code "167") (name "PIA-B4") (class "Default")
      (node (ref "CORE-IO") (pin "17") (pinfunction "17_17") (pintype "passive"))
      (node (ref "IC19") (pin "2") (pinfunction "B_2") (pintype "input"))
    )
    (net (code "168") (name "PIA-B5") (class "Default")
      (node (ref "CORE-IO") (pin "18") (pinfunction "18_18") (pintype "passive"))
      (node (ref "IC19") (pin "3") (pinfunction "C_3") (pintype "input"))
    )
    (net (code "169") (name "PIA-B6") (class "Default")
      (node (ref "CORE-IO") (pin "19") (pinfunction "19_19") (pintype "passive"))
      (node (ref "IC10") (pin "6") (pinfunction "G1_6") (pintype "input"))
      (node (ref "IC9") (pin "4") (pinfunction "G2A_4") (pintype "input"))
    )
    (net (code "170") (name "PIA-B7") (class "Default")
      (node (ref "CORE-IO") (pin "20") (pinfunction "20_20") (pintype "passive"))
      (node (ref "DEVSEL") (pin "2") (pinfunction "2_2") (pintype "passive"))
      (node (ref "IC19") (pin "5") (pinfunction "G2B_5") (pintype "input"))
    )
    (net (code "171") (name "VCC") (class "Default")
      (node (ref "BYP1") (pin "1") (pinfunction "1_1") (pintype "passive"))
      (node (ref "BYP10") (pin "1") (pinfunction "1_1") (pintype "passive"))
      (node (ref "BYP11") (pin "1") (pinfunction "1_1") (pintype "passive"))
      (node (ref "BYP12") (pin "1") (pinfunction "1_1") (pintype "passive"))
      (node (ref "BYP13") (pin "1") (pinfunction "1_1") (pintype "passive"))
      (node (ref "BYP14") (pin "1") (pinfunction "1_1") (pintype "passive"))
      (node (ref "BYP15") (pin "1") (pinfunction "1_1") (pintype "passive"))
      (node (ref "BYP16") (pin "1") (pinfunction "1_1") (pintype "passive"))
      (node (ref "BYP17") (pin "1") (pinfunction "1_1") (pintype "passive"))
      (node (ref "BYP18") (pin "1") (pinfunction "1_1") (pintype "passive"))
      (node (ref "BYP19") (pin "1") (pinfunction "1_1") (pintype "passive"))
      (node (ref "BYP2") (pin "1") (pinfunction "1_1") (pintype "passive"))
      (node (ref "BYP20") (pin "1") (pinfunction "1_1") (pintype "passive"))
      (node (ref "BYP3") (pin "1") (pinfunction "1_1") (pintype "passive"))
      (node (ref "BYP4") (pin "1") (pinfunction "1_1") (pintype "passive"))
      (node (ref "BYP5") (pin "1") (pinfunction "1_1") (pintype "passive"))
      (node (ref "BYP6") (pin "1") (pinfunction "1_1") (pintype "passive"))
      (node (ref "BYP7") (pin "1") (pinfunction "1_1") (pintype "passive"))
      (node (ref "BYP8") (pin "1") (pinfunction "1_1") (pintype "passive"))
      (node (ref "BYP9") (pin "1") (pinfunction "1_1") (pintype "passive"))
      (node (ref "CORE-IO") (pin "12") (pinfunction "12_12") (pintype "passive"))
      (node (ref "CORE-IO") (pin "9") (pinfunction "9_9") (pintype "passive"))
      (node (ref "IC11") (pin "11") (pinfunction "ENC_11") (pintype "input"))
      (node (ref "IC12") (pin "11") (pinfunction "ENC_11") (pintype "input"))
      (node (ref "IC13") (pin "11") (pinfunction "ENC_11") (pintype "input"))
      (node (ref "IC14") (pin "11") (pinfunction "ENC_11") (pintype "input"))
      (node (ref "IC15") (pin "11") (pinfunction "ENC_11") (pintype "input"))
      (node (ref "IC16") (pin "11") (pinfunction "ENC_11") (pintype "input"))
      (node (ref "IC17") (pin "11") (pinfunction "ENC_11") (pintype "input"))
      (node (ref "IC18") (pin "11") (pinfunction "ENC_11") (pintype "input"))
      (node (ref "IC19") (pin "6") (pinfunction "G1_6") (pintype "input"))
      (node (ref "IC9") (pin "6") (pinfunction "G1_6") (pintype "input"))
      (node (ref "JP2") (pin "2") (pinfunction "2_2") (pintype "passive"))
    )
    (net (code "172") (name "~{OC}") (class "Default")
      (node (ref "!OC") (pin "2") (pinfunction "2_2") (pintype "passive"))
      (node (ref "IC1") (pin "1") (pinfunction "OC_1") (pintype "input"))
      (node (ref "IC2") (pin "1") (pinfunction "OC_1") (pintype "input"))
      (node (ref "IC3") (pin "1") (pinfunction "OC_1") (pintype "input"))
      (node (ref "IC4") (pin "1") (pinfunction "OC_1") (pintype "input"))
      (node (ref "IC5") (pin "1") (pinfunction "OC_1") (pintype "input"))
      (node (ref "IC6") (pin "1") (pinfunction "OC_1") (pintype "input"))
      (node (ref "IC7") (pin "1") (pinfunction "OC_1") (pintype "input"))
      (node (ref "IC8") (pin "1") (pinfunction "OC_1") (pintype "input"))
    )
  )
)
